# Server_Ethernet.net
KiCad netlist of a schematic drawn in Altium Designer
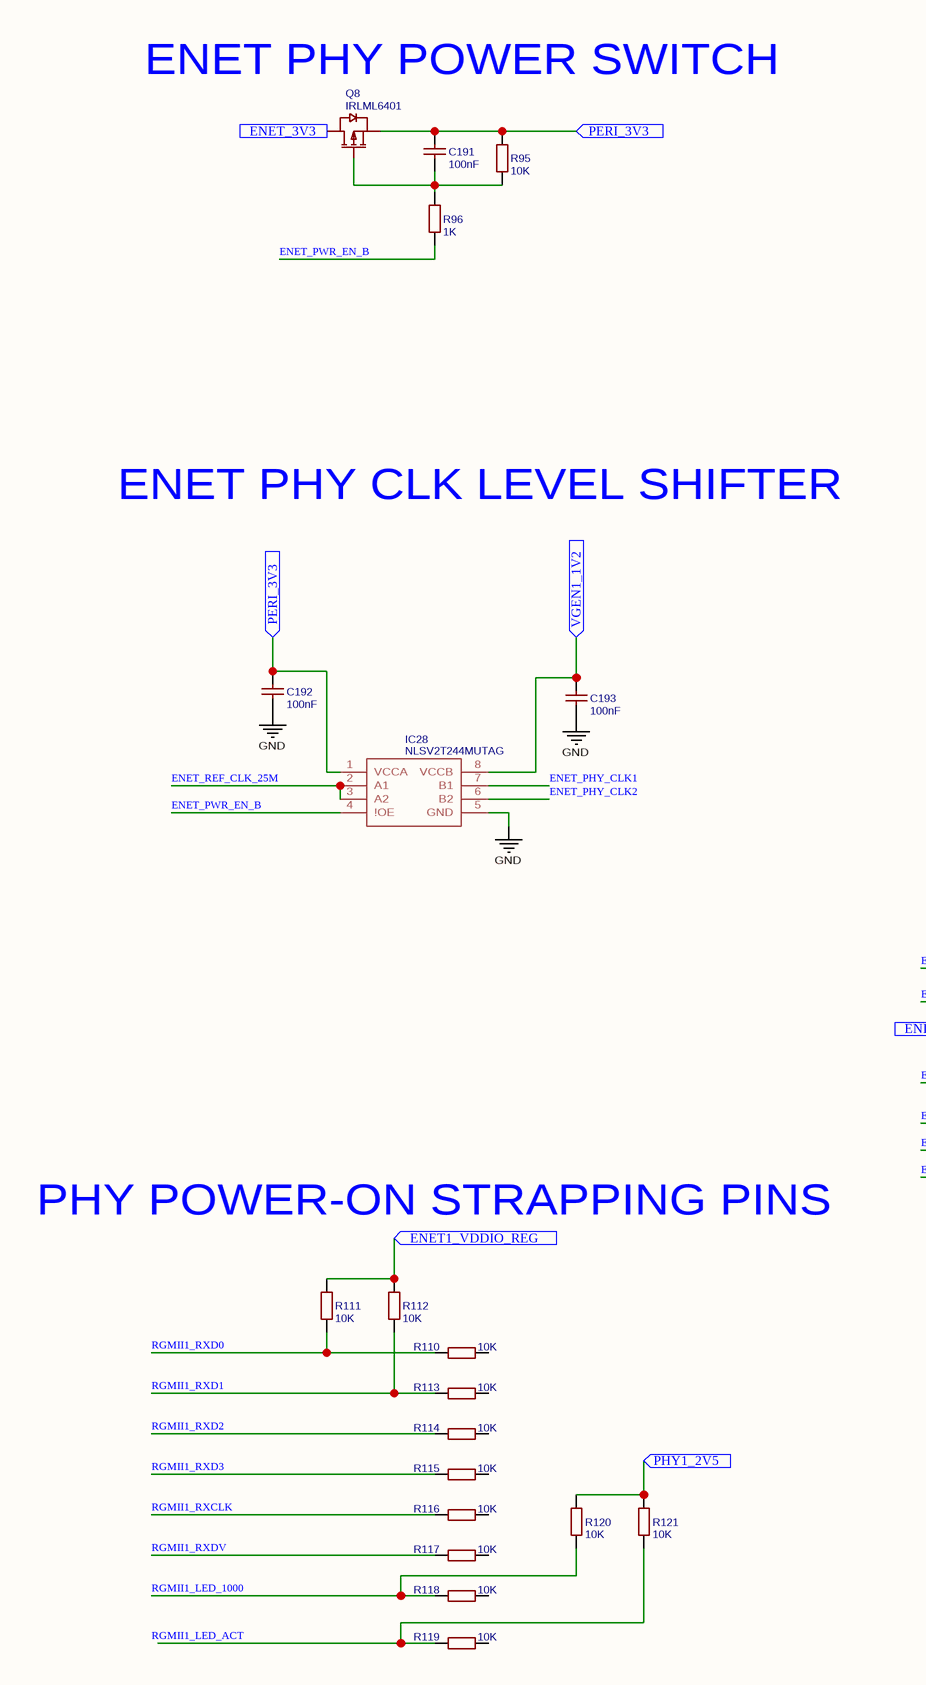
[diagram p0: Server Ethernet.schdoc, left]
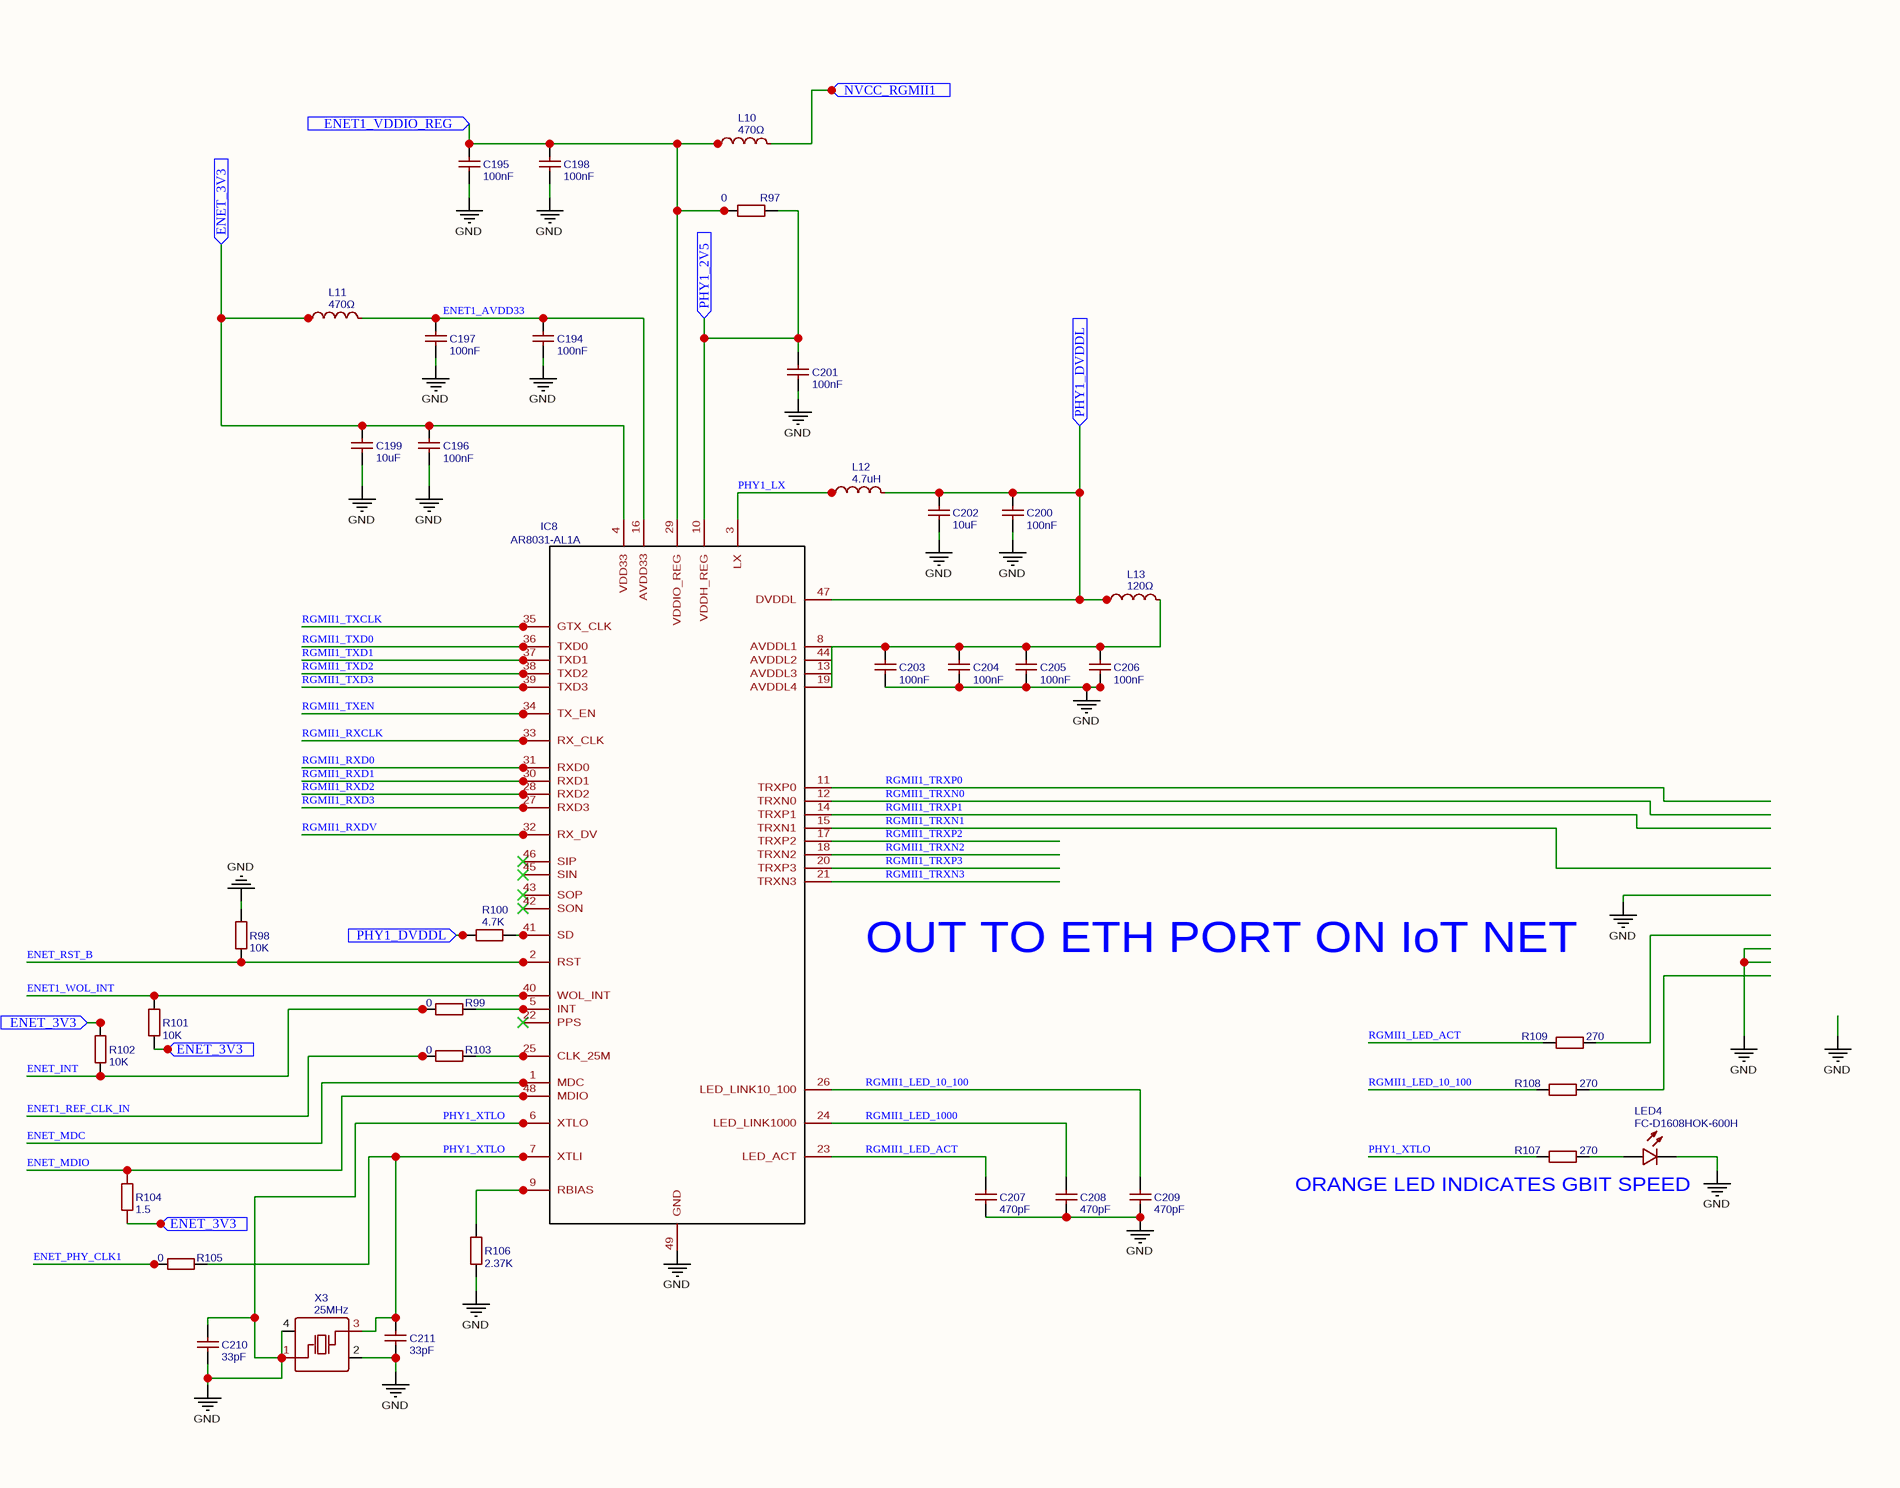
[diagram p1: Server Ethernet.schdoc, right]

(export (version "E")
  (design (tool "Eeschema 10.0.6"))
  (components
    (comp (ref "C191")
      (value "100nF")
      (fields
        (field (name "BOM_MANUFACTURER PART") "0603B104K250")
        (field (name "BOM_SUPPLIER PART") "C83054")
      )
      (libsource (lib "altium-import") (part "root_1_100nF_"))
    )
    (comp (ref "C192")
      (value "100nF")
      (fields
        (field (name "BOM_MANUFACTURER PART") "0603B104K250")
        (field (name "BOM_SUPPLIER PART") "C83054")
      )
      (libsource (lib "altium-import") (part "root_1_100nF_"))
    )
    (comp (ref "C193")
      (value "100nF")
      (fields
        (field (name "BOM_MANUFACTURER PART") "0603B104K250")
        (field (name "BOM_SUPPLIER PART") "C83054")
      )
      (libsource (lib "altium-import") (part "root_1_100nF_"))
    )
    (comp (ref "C194")
      (value "100nF")
      (fields
        (field (name "BOM_MANUFACTURER PART") "0603B104K250")
        (field (name "BOM_SUPPLIER PART") "C83054")
      )
      (libsource (lib "altium-import") (part "root_1_100nF_"))
    )
    (comp (ref "C195")
      (value "100nF")
      (fields
        (field (name "BOM_MANUFACTURER PART") "0603B104K250")
        (field (name "BOM_SUPPLIER PART") "C83054")
      )
      (libsource (lib "altium-import") (part "root_1_100nF_"))
    )
    (comp (ref "C196")
      (value "100nF")
      (fields
        (field (name "BOM_MANUFACTURER PART") "0603B104K250")
        (field (name "BOM_SUPPLIER PART") "C83054")
      )
      (libsource (lib "altium-import") (part "root_1_100nF_"))
    )
    (comp (ref "C197")
      (value "100nF")
      (fields
        (field (name "BOM_MANUFACTURER PART") "0603B104K250")
        (field (name "BOM_SUPPLIER PART") "C83054")
      )
      (libsource (lib "altium-import") (part "root_1_100nF_"))
    )
    (comp (ref "C198")
      (value "100nF")
      (fields
        (field (name "BOM_MANUFACTURER PART") "0603B104K250")
        (field (name "BOM_SUPPLIER PART") "C83054")
      )
      (libsource (lib "altium-import") (part "root_1_100nF_"))
    )
    (comp (ref "C199")
      (value "10uF")
      (fields
        (field (name "BOM_MANUFACTURER PART") "CL21A106KAYNNNE")
        (field (name "BOM_SUPPLIER PART") "C15850")
      )
      (libsource (lib "altium-import") (part "root_1_10uF_"))
    )
    (comp (ref "C200")
      (value "100nF")
      (fields
        (field (name "BOM_MANUFACTURER PART") "0603B104K250")
        (field (name "BOM_SUPPLIER PART") "C83054")
      )
      (libsource (lib "altium-import") (part "root_1_100nF_"))
    )
    (comp (ref "C201")
      (value "100nF")
      (fields
        (field (name "BOM_MANUFACTURER PART") "0603B104K250")
        (field (name "BOM_SUPPLIER PART") "C83054")
      )
      (libsource (lib "altium-import") (part "root_1_100nF_"))
    )
    (comp (ref "C202")
      (value "10uF")
      (fields
        (field (name "BOM_MANUFACTURER PART") "CL21A106KAYNNNE")
        (field (name "BOM_SUPPLIER PART") "C15850")
      )
      (libsource (lib "altium-import") (part "root_1_10uF_"))
    )
    (comp (ref "C203")
      (value "100nF")
      (fields
        (field (name "BOM_MANUFACTURER PART") "0603B104K250")
        (field (name "BOM_SUPPLIER PART") "C83054")
      )
      (libsource (lib "altium-import") (part "root_1_100nF_"))
    )
    (comp (ref "C204")
      (value "100nF")
      (fields
        (field (name "BOM_MANUFACTURER PART") "0603B104K250")
        (field (name "BOM_SUPPLIER PART") "C83054")
      )
      (libsource (lib "altium-import") (part "root_1_100nF_"))
    )
    (comp (ref "C205")
      (value "100nF")
      (fields
        (field (name "BOM_MANUFACTURER PART") "0603B104K250")
        (field (name "BOM_SUPPLIER PART") "C83054")
      )
      (libsource (lib "altium-import") (part "root_1_100nF_"))
    )
    (comp (ref "C206")
      (value "100nF")
      (fields
        (field (name "BOM_MANUFACTURER PART") "0603B104K250")
        (field (name "BOM_SUPPLIER PART") "C83054")
      )
      (libsource (lib "altium-import") (part "root_1_100nF_"))
    )
    (comp (ref "C207")
      (value "470pF")
      (fields
        (field (name "BOM_MANUFACTURER PART") "0805B471K500NT")
        (field (name "BOM_SUPPLIER PART") "C1743")
      )
      (libsource (lib "altium-import") (part "root_1_470pF_"))
    )
    (comp (ref "C208")
      (value "470pF")
      (fields
        (field (name "BOM_MANUFACTURER PART") "0805B471K500NT")
        (field (name "BOM_SUPPLIER PART") "C1743")
      )
      (libsource (lib "altium-import") (part "root_1_470pF_"))
    )
    (comp (ref "C209")
      (value "470pF")
      (fields
        (field (name "BOM_MANUFACTURER PART") "0805B471K500NT")
        (field (name "BOM_SUPPLIER PART") "C1743")
      )
      (libsource (lib "altium-import") (part "root_1_470pF_"))
    )
    (comp (ref "C210")
      (value "33pF")
      (fields
        (field (name "BOM_MANUFACTURER PART") "0402CG330J500NT")
        (field (name "BOM_SUPPLIER PART") "C1562")
      )
      (libsource (lib "altium-import") (part "root_1_33pF_"))
    )
    (comp (ref "C211")
      (value "33pF")
      (fields
        (field (name "BOM_MANUFACTURER PART") "0402CG330J500NT")
        (field (name "BOM_SUPPLIER PART") "C1562")
      )
      (libsource (lib "altium-import") (part "root_1_33pF_"))
    )
    (comp (ref "IC8")
      (value "AR8031-AL1A")
      (fields (field (name "CONTRIBUTOR") "Ke'Ondrae_Mell"))
      (libsource (lib "altium-import") (part "root_0_AR8031-AL1A_"))
    )
    (comp (ref "IC28")
      (value "NLSV2T244MUTAG")
      (fields (field (name "CONTRIBUTOR") "Ke'Ondrae_Mell"))
      (libsource (lib "altium-import") (part "root_0_NLSV2T244MUTAG_"))
    )
    (comp (ref "L10")
      (value "470Ω")
      (fields
        (field (name "BOM_MANUFACTURER PART") "GZ1608D471TF")
        (field (name "BOM_SUPPLIER PART") "C89921")
      )
      (libsource (lib "altium-import") (part "root_0_470Ω_"))
    )
    (comp (ref "L11")
      (value "470Ω")
      (fields
        (field (name "BOM_MANUFACTURER PART") "GZ1608D471TF")
        (field (name "BOM_SUPPLIER PART") "C89921")
      )
      (libsource (lib "altium-import") (part "root_0_470Ω_"))
    )
    (comp (ref "L12")
      (value "4.7uH")
      (fields
        (field (name "BOM_MANUFACTURER PART") "MLF2012A4R7KT000")
        (field (name "BOM_SUPPLIER PART") "C76736")
      )
      (libsource (lib "altium-import") (part "root_0_4.7uH_"))
    )
    (comp (ref "L13")
      (value "120Ω")
      (fields
        (field (name "BOM_MANUFACTURER PART") "BLM18PG121SN1D")
        (field (name "BOM_SUPPLIER PART") "C73100")
      )
      (libsource (lib "altium-import") (part "root_0_120Ω_"))
    )
    (comp (ref "LED4")
      (value "FC-D1608HOK-600H")
      (fields (field (name "BOM_SUPPLIER PART") "C84269"))
      (libsource (lib "altium-import") (part "root_0_FC-D1608HOK-600H_"))
    )
    (comp (ref "Q8")
      (value "IRLML6401")
      (fields (field (name "BOM_SUPPLIER PART") "C236925") (field (name "CONTRIBUTOR") "LCSC"))
      (libsource (lib "altium-import") (part "root_1_IRLML6401_"))
    )
    (comp (ref "R95")
      (value "10K")
      (fields
        (field (name "BOM_MANUFACTURER PART") "0402WGF1002TCE")
        (field (name "BOM_SUPPLIER PART") "C25744")
      )
      (libsource (lib "altium-import") (part "root_1_10K_"))
    )
    (comp (ref "R96")
      (value "1K")
      (fields
        (field (name "BOM_MANUFACTURER PART") "0402WGF1001TCE")
        (field (name "BOM_SUPPLIER PART") "C11702")
      )
      (libsource (lib "altium-import") (part "root_1_1K_"))
    )
    (comp (ref "R97")
      (value "0")
      (fields
        (field (name "BOM_MANUFACTURER PART") "RK73Z1ETTP")
        (field (name "BOM_SUPPLIER PART") "C131359")
      )
      (libsource (lib "altium-import") (part "root_0_0_"))
    )
    (comp (ref "R98")
      (value "10K")
      (fields
        (field (name "BOM_MANUFACTURER PART") "0402WGF1002TCE")
        (field (name "BOM_SUPPLIER PART") "C25744")
      )
      (libsource (lib "altium-import") (part "root_1_10K_"))
    )
    (comp (ref "R99")
      (value "0")
      (fields
        (field (name "BOM_MANUFACTURER PART") "RK73Z1ETTP")
        (field (name "BOM_SUPPLIER PART") "C131359")
      )
      (libsource (lib "altium-import") (part "root_0_0_"))
    )
    (comp (ref "R100")
      (value "4.7K")
      (fields
        (field (name "BOM_MANUFACTURER PART") "0402WGF4701TCE")
        (field (name "BOM_SUPPLIER PART") "C25900")
      )
      (libsource (lib "altium-import") (part "root_0_4.7K_"))
    )
    (comp (ref "R101")
      (value "10K")
      (fields
        (field (name "BOM_MANUFACTURER PART") "0402WGF1002TCE")
        (field (name "BOM_SUPPLIER PART") "C25744")
      )
      (libsource (lib "altium-import") (part "root_1_10K_"))
    )
    (comp (ref "R102")
      (value "10K")
      (fields
        (field (name "BOM_MANUFACTURER PART") "0402WGF1002TCE")
        (field (name "BOM_SUPPLIER PART") "C25744")
      )
      (libsource (lib "altium-import") (part "root_1_10K_"))
    )
    (comp (ref "R103")
      (value "0")
      (fields
        (field (name "BOM_MANUFACTURER PART") "RK73Z1ETTP")
        (field (name "BOM_SUPPLIER PART") "C131359")
      )
      (libsource (lib "altium-import") (part "root_0_0_"))
    )
    (comp (ref "R104")
      (value "1.5")
      (fields
        (field (name "BOM_SUPPLIER PART") "C270642")
        (field (name "BOM_MANUFACTURER PART") "0402WGF150KTCE")
        (field (name "CONTRIBUTOR") "LCSC")
      )
      (libsource (lib "altium-import") (part "root_1_1.5_"))
    )
    (comp (ref "R105")
      (value "0")
      (fields
        (field (name "BOM_MANUFACTURER PART") "RK73Z1ETTP")
        (field (name "BOM_SUPPLIER PART") "C131359")
      )
      (libsource (lib "altium-import") (part "root_0_0_"))
    )
    (comp (ref "R106")
      (value "2.37K")
      (fields
        (field (name "BOM_MANUFACTURER PART") "0402WGF2371TCE")
        (field (name "BOM_SUPPLIER PART") "C25881")
      )
      (libsource (lib "altium-import") (part "root_1_2.37K_"))
    )
    (comp (ref "R107")
      (value "270")
      (fields
        (field (name "BOM_MANUFACTURER PART") "0603WAF2700T5E")
        (field (name "BOM_SUPPLIER PART") "C22966")
      )
      (libsource (lib "altium-import") (part "root_0_270_"))
    )
    (comp (ref "R108")
      (value "270")
      (fields
        (field (name "BOM_MANUFACTURER PART") "0603WAF2700T5E")
        (field (name "BOM_SUPPLIER PART") "C22966")
      )
      (libsource (lib "altium-import") (part "root_0_270_"))
    )
    (comp (ref "R109")
      (value "270")
      (fields
        (field (name "BOM_MANUFACTURER PART") "0603WAF2700T5E")
        (field (name "BOM_SUPPLIER PART") "C22966")
      )
      (libsource (lib "altium-import") (part "root_0_270_"))
    )
    (comp (ref "R110")
      (value "10K")
      (fields
        (field (name "BOM_MANUFACTURER PART") "0402WGF1002TCE")
        (field (name "BOM_SUPPLIER PART") "C25744")
      )
      (libsource (lib "altium-import") (part "root_2_10K_"))
    )
    (comp (ref "R111")
      (value "10K")
      (fields
        (field (name "BOM_MANUFACTURER PART") "0402WGF1002TCE")
        (field (name "BOM_SUPPLIER PART") "C25744")
      )
      (libsource (lib "altium-import") (part "root_1_10K_"))
    )
    (comp (ref "R112")
      (value "10K")
      (fields
        (field (name "BOM_MANUFACTURER PART") "0402WGF1002TCE")
        (field (name "BOM_SUPPLIER PART") "C25744")
      )
      (libsource (lib "altium-import") (part "root_1_10K_"))
    )
    (comp (ref "R113")
      (value "10K")
      (fields
        (field (name "BOM_MANUFACTURER PART") "0402WGF1002TCE")
        (field (name "BOM_SUPPLIER PART") "C25744")
      )
      (libsource (lib "altium-import") (part "root_2_10K_"))
    )
    (comp (ref "R114")
      (value "10K")
      (fields
        (field (name "BOM_MANUFACTURER PART") "0402WGF1002TCE")
        (field (name "BOM_SUPPLIER PART") "C25744")
      )
      (libsource (lib "altium-import") (part "root_2_10K_"))
    )
    (comp (ref "R115")
      (value "10K")
      (fields
        (field (name "BOM_MANUFACTURER PART") "0402WGF1002TCE")
        (field (name "BOM_SUPPLIER PART") "C25744")
      )
      (libsource (lib "altium-import") (part "root_2_10K_"))
    )
    (comp (ref "R116")
      (value "10K")
      (fields
        (field (name "BOM_MANUFACTURER PART") "0402WGF1002TCE")
        (field (name "BOM_SUPPLIER PART") "C25744")
      )
      (libsource (lib "altium-import") (part "root_2_10K_"))
    )
    (comp (ref "R117")
      (value "10K")
      (fields
        (field (name "BOM_MANUFACTURER PART") "0402WGF1002TCE")
        (field (name "BOM_SUPPLIER PART") "C25744")
      )
      (libsource (lib "altium-import") (part "root_2_10K_"))
    )
    (comp (ref "R118")
      (value "10K")
      (fields
        (field (name "BOM_MANUFACTURER PART") "0402WGF1002TCE")
        (field (name "BOM_SUPPLIER PART") "C25744")
      )
      (libsource (lib "altium-import") (part "root_2_10K_"))
    )
    (comp (ref "R119")
      (value "10K")
      (fields
        (field (name "BOM_MANUFACTURER PART") "0402WGF1002TCE")
        (field (name "BOM_SUPPLIER PART") "C25744")
      )
      (libsource (lib "altium-import") (part "root_2_10K_"))
    )
    (comp (ref "R120")
      (value "10K")
      (fields
        (field (name "BOM_MANUFACTURER PART") "0402WGF1002TCE")
        (field (name "BOM_SUPPLIER PART") "C25744")
      )
      (libsource (lib "altium-import") (part "root_3_10K_"))
    )
    (comp (ref "R121")
      (value "10K")
      (fields
        (field (name "BOM_MANUFACTURER PART") "0402WGF1002TCE")
        (field (name "BOM_SUPPLIER PART") "C25744")
      )
      (libsource (lib "altium-import") (part "root_3_10K_"))
    )
    (comp (ref "X3")
      (value "25MHz")
      (fields
        (field (name "BOM_MANUFACTURER PART") "X322525MOB4SI")
        (field (name "BOM_SUPPLIER PART") "C9006")
      )
      (libsource (lib "altium-import") (part "root_0_25MHz_"))
    )
  )
  (nets
    (net (code "1") (name "/ENET1_AVDD33") (class "Default")
      (node (ref "C194") (pin "2") (pinfunction "2_2") (pintype "passive"))
      (node (ref "C197") (pin "2") (pinfunction "2_2") (pintype "passive"))
      (node (ref "IC8") (pin "16") (pinfunction "AVDD33_16") (pintype "passive"))
      (node (ref "L11") (pin "2") (pinfunction "2_2") (pintype "passive"))
    )
    (net (code "2") (name "/ENET1_REF_CLK_IN") (class "Default")
      (node (ref "R103") (pin "1") (pinfunction "1_1") (pintype "passive"))
    )
    (net (code "3") (name "/ENET1_VDDIO_REG") (class "Default")
      (node (ref "C195") (pin "2") (pinfunction "2_2") (pintype "passive"))
      (node (ref "C198") (pin "2") (pinfunction "2_2") (pintype "passive"))
      (node (ref "IC8") (pin "29") (pinfunction "VDDIO_REG_29") (pintype "passive"))
      (node (ref "L10") (pin "1") (pinfunction "1_1") (pintype "passive"))
      (node (ref "R111") (pin "2") (pinfunction "2_2") (pintype "passive"))
      (node (ref "R112") (pin "2") (pinfunction "2_2") (pintype "passive"))
      (node (ref "R97") (pin "1") (pinfunction "1_1") (pintype "passive"))
    )
    (net (code "4") (name "/ENET1_WOL_INT") (class "Default")
      (node (ref "IC8") (pin "40") (pinfunction "WOL_INT_40") (pintype "passive"))
      (node (ref "R101") (pin "2") (pinfunction "2_2") (pintype "passive"))
    )
    (net (code "5") (name "/ENET_3V3") (class "Default")
      (node (ref "C196") (pin "2") (pinfunction "2_2") (pintype "passive"))
      (node (ref "C199") (pin "2") (pinfunction "2_2") (pintype "passive"))
      (node (ref "IC8") (pin "4") (pinfunction "VDD33_4") (pintype "passive"))
      (node (ref "L11") (pin "1") (pinfunction "1_1") (pintype "passive"))
      (node (ref "Q8") (pin "3") (pinfunction "D_3") (pintype "passive"))
      (node (ref "R101") (pin "1") (pinfunction "1_1") (pintype "passive"))
      (node (ref "R102") (pin "2") (pinfunction "2_2") (pintype "passive"))
      (node (ref "R104") (pin "1") (pinfunction "1_1") (pintype "passive"))
    )
    (net (code "6") (name "/ENET_INT") (class "Default")
      (node (ref "R102") (pin "1") (pinfunction "1_1") (pintype "passive"))
      (node (ref "R99") (pin "1") (pinfunction "1_1") (pintype "passive"))
    )
    (net (code "7") (name "/ENET_MDC") (class "Default")
      (node (ref "IC8") (pin "1") (pinfunction "MDC_1") (pintype "passive"))
    )
    (net (code "8") (name "/ENET_MDIO") (class "Default")
      (node (ref "IC8") (pin "48") (pinfunction "MDIO_48") (pintype "passive"))
      (node (ref "R104") (pin "2") (pinfunction "2_2") (pintype "passive"))
    )
    (net (code "9") (name "/ENET_PHY_CLK1") (class "Default")
      (node (ref "IC28") (pin "7") (pinfunction "B1_7") (pintype "passive"))
      (node (ref "R105") (pin "1") (pinfunction "1_1") (pintype "passive"))
    )
    (net (code "10") (name "/ENET_PHY_CLK2") (class "Default")
      (node (ref "IC28") (pin "6") (pinfunction "B2_6") (pintype "passive"))
    )
    (net (code "11") (name "/ENET_PWR_EN_B") (class "Default")
      (node (ref "IC28") (pin "4") (pinfunction "!OE_4") (pintype "passive"))
      (node (ref "R96") (pin "1") (pinfunction "1_1") (pintype "passive"))
    )
    (net (code "12") (name "/ENET_REF_CLK_25M") (class "Default")
      (node (ref "IC28") (pin "2") (pinfunction "A1_2") (pintype "passive"))
      (node (ref "IC28") (pin "3") (pinfunction "A2_3") (pintype "passive"))
    )
    (net (code "13") (name "/ENET_RST_B") (class "Default")
      (node (ref "IC8") (pin "2") (pinfunction "RST_2") (pintype "passive"))
      (node (ref "R98") (pin "1") (pinfunction "1_1") (pintype "passive"))
    )
    (net (code "14") (name "/NVCC_RGMII1") (class "Default")
      (node (ref "L10") (pin "2") (pinfunction "2_2") (pintype "passive"))
    )
    (net (code "15") (name "/PERI_3V3") (class "Default")
      (node (ref "C191") (pin "2") (pinfunction "2_2") (pintype "passive"))
      (node (ref "C192") (pin "2") (pinfunction "2_2") (pintype "passive"))
      (node (ref "IC28") (pin "1") (pinfunction "VCCA_1") (pintype "passive"))
      (node (ref "Q8") (pin "2") (pinfunction "S_2") (pintype "passive"))
      (node (ref "R95") (pin "2") (pinfunction "2_2") (pintype "passive"))
    )
    (net (code "16") (name "/PHY1_2V5") (class "Default")
      (node (ref "C201") (pin "2") (pinfunction "2_2") (pintype "passive"))
      (node (ref "IC8") (pin "10") (pinfunction "VDDH_REG_10") (pintype "passive"))
      (node (ref "R120") (pin "1") (pinfunction "1_1") (pintype "passive"))
      (node (ref "R121") (pin "1") (pinfunction "1_1") (pintype "passive"))
      (node (ref "R97") (pin "2") (pinfunction "2_2") (pintype "passive"))
    )
    (net (code "17") (name "/PHY1_DVDDL") (class "Default")
      (node (ref "C200") (pin "2") (pinfunction "2_2") (pintype "passive"))
      (node (ref "C202") (pin "2") (pinfunction "2_2") (pintype "passive"))
      (node (ref "IC8") (pin "47") (pinfunction "DVDDL_47") (pintype "passive"))
      (node (ref "L12") (pin "2") (pinfunction "2_2") (pintype "passive"))
      (node (ref "L13") (pin "1") (pinfunction "1_1") (pintype "passive"))
      (node (ref "R100") (pin "1") (pinfunction "1_1") (pintype "passive"))
    )
    (net (code "18") (name "/PHY1_LX") (class "Default")
      (node (ref "IC8") (pin "3") (pinfunction "LX_3") (pintype "passive"))
      (node (ref "L12") (pin "1") (pinfunction "1_1") (pintype "passive"))
    )
    (net (code "19") (name "/RGMII1_LED_10_100") (class "Default")
      (node (ref "C209") (pin "2") (pinfunction "2_2") (pintype "passive"))
      (node (ref "IC8") (pin "26") (pinfunction "LED_LINK10_100_26") (pintype "passive"))
      (node (ref "R108") (pin "1") (pinfunction "1_1") (pintype "passive"))
    )
    (net (code "20") (name "/RGMII1_LED_1000") (class "Default")
      (node (ref "C208") (pin "2") (pinfunction "2_2") (pintype "passive"))
      (node (ref "IC8") (pin "24") (pinfunction "LED_LINK1000_24") (pintype "passive"))
      (node (ref "R118") (pin "2") (pinfunction "2_2") (pintype "passive"))
      (node (ref "R120") (pin "2") (pinfunction "2_2") (pintype "passive"))
    )
    (net (code "21") (name "/RGMII1_LED_ACT") (class "Default")
      (node (ref "C207") (pin "2") (pinfunction "2_2") (pintype "passive"))
      (node (ref "IC8") (pin "23") (pinfunction "LED_ACT_23") (pintype "passive"))
      (node (ref "R109") (pin "1") (pinfunction "1_1") (pintype "passive"))
    )
    (net (code "22") (name "/RGMII1_RXCLK") (class "Default")
      (node (ref "IC8") (pin "33") (pinfunction "RX_CLK_33") (pintype "passive"))
      (node (ref "R116") (pin "2") (pinfunction "2_2") (pintype "passive"))
    )
    (net (code "23") (name "/RGMII1_RXD0") (class "Default")
      (node (ref "IC8") (pin "31") (pinfunction "RXD0_31") (pintype "passive"))
      (node (ref "R110") (pin "2") (pinfunction "2_2") (pintype "passive"))
      (node (ref "R111") (pin "1") (pinfunction "1_1") (pintype "passive"))
    )
    (net (code "24") (name "/RGMII1_RXD1") (class "Default")
      (node (ref "IC8") (pin "30") (pinfunction "RXD1_30") (pintype "passive"))
      (node (ref "R112") (pin "1") (pinfunction "1_1") (pintype "passive"))
      (node (ref "R113") (pin "2") (pinfunction "2_2") (pintype "passive"))
    )
    (net (code "25") (name "/RGMII1_RXD2") (class "Default")
      (node (ref "IC8") (pin "28") (pinfunction "RXD2_28") (pintype "passive"))
      (node (ref "R114") (pin "2") (pinfunction "2_2") (pintype "passive"))
    )
    (net (code "26") (name "/RGMII1_RXD3") (class "Default")
      (node (ref "IC8") (pin "27") (pinfunction "RXD3_27") (pintype "passive"))
      (node (ref "R115") (pin "2") (pinfunction "2_2") (pintype "passive"))
    )
    (net (code "27") (name "/RGMII1_RXDV") (class "Default")
      (node (ref "IC8") (pin "32") (pinfunction "RX_DV_32") (pintype "passive"))
      (node (ref "R117") (pin "2") (pinfunction "2_2") (pintype "passive"))
    )
    (net (code "28") (name "/RGMII1_TRXN0") (class "Default")
      (node (ref "IC8") (pin "12") (pinfunction "TRXN0_12") (pintype "passive"))
    )
    (net (code "29") (name "/RGMII1_TRXN1") (class "Default")
      (node (ref "IC8") (pin "15") (pinfunction "TRXN1_15") (pintype "passive"))
    )
    (net (code "30") (name "/RGMII1_TRXN2") (class "Default")
      (node (ref "IC8") (pin "18") (pinfunction "TRXN2_18") (pintype "passive"))
    )
    (net (code "31") (name "/RGMII1_TRXN3") (class "Default")
      (node (ref "IC8") (pin "21") (pinfunction "TRXN3_21") (pintype "passive"))
    )
    (net (code "32") (name "/RGMII1_TRXP0") (class "Default")
      (node (ref "IC8") (pin "11") (pinfunction "TRXP0_11") (pintype "passive"))
    )
    (net (code "33") (name "/RGMII1_TRXP1") (class "Default")
      (node (ref "IC8") (pin "14") (pinfunction "TRXP1_14") (pintype "passive"))
    )
    (net (code "34") (name "/RGMII1_TRXP2") (class "Default")
      (node (ref "IC8") (pin "17") (pinfunction "TRXP2_17") (pintype "passive"))
    )
    (net (code "35") (name "/RGMII1_TRXP3") (class "Default")
      (node (ref "IC8") (pin "20") (pinfunction "TRXP3_20") (pintype "passive"))
    )
    (net (code "36") (name "/RGMII1_TXCLK") (class "Default")
      (node (ref "IC8") (pin "35") (pinfunction "GTX_CLK_35") (pintype "passive"))
    )
    (net (code "37") (name "/RGMII1_TXD0") (class "Default")
      (node (ref "IC8") (pin "36") (pinfunction "TXD0_36") (pintype "passive"))
    )
    (net (code "38") (name "/RGMII1_TXD1") (class "Default")
      (node (ref "IC8") (pin "37") (pinfunction "TXD1_37") (pintype "passive"))
    )
    (net (code "39") (name "/RGMII1_TXD2") (class "Default")
      (node (ref "IC8") (pin "38") (pinfunction "TXD2_38") (pintype "passive"))
    )
    (net (code "40") (name "/RGMII1_TXD3") (class "Default")
      (node (ref "IC8") (pin "39") (pinfunction "TXD3_39") (pintype "passive"))
    )
    (net (code "41") (name "/RGMII1_TXEN") (class "Default")
      (node (ref "IC8") (pin "34") (pinfunction "TX_EN_34") (pintype "passive"))
    )
    (net (code "42") (name "/VGEN1_1V2") (class "Default")
      (node (ref "C193") (pin "2") (pinfunction "2_2") (pintype "passive"))
      (node (ref "IC28") (pin "8") (pinfunction "VCCB_8") (pintype "passive"))
    )
    (net (code "43") (name "GND") (class "Default")
      (node (ref "C192") (pin "1") (pinfunction "1_1") (pintype "passive"))
      (node (ref "C193") (pin "1") (pinfunction "1_1") (pintype "passive"))
      (node (ref "C194") (pin "1") (pinfunction "1_1") (pintype "passive"))
      (node (ref "C195") (pin "1") (pinfunction "1_1") (pintype "passive"))
      (node (ref "C196") (pin "1") (pinfunction "1_1") (pintype "passive"))
      (node (ref "C197") (pin "1") (pinfunction "1_1") (pintype "passive"))
      (node (ref "C198") (pin "1") (pinfunction "1_1") (pintype "passive"))
      (node (ref "C199") (pin "1") (pinfunction "1_1") (pintype "passive"))
      (node (ref "C200") (pin "1") (pinfunction "1_1") (pintype "passive"))
      (node (ref "C201") (pin "1") (pinfunction "1_1") (pintype "passive"))
      (node (ref "C202") (pin "1") (pinfunction "1_1") (pintype "passive"))
      (node (ref "C203") (pin "1") (pinfunction "1_1") (pintype "passive"))
      (node (ref "C204") (pin "1") (pinfunction "1_1") (pintype "passive"))
      (node (ref "C205") (pin "1") (pinfunction "1_1") (pintype "passive"))
      (node (ref "C206") (pin "1") (pinfunction "1_1") (pintype "passive"))
      (node (ref "C207") (pin "1") (pinfunction "1_1") (pintype "passive"))
      (node (ref "C208") (pin "1") (pinfunction "1_1") (pintype "passive"))
      (node (ref "C209") (pin "1") (pinfunction "1_1") (pintype "passive"))
      (node (ref "C210") (pin "1") (pinfunction "1_1") (pintype "passive"))
      (node (ref "C210") (pin "2") (pinfunction "2_2") (pintype "passive"))
      (node (ref "C211") (pin "1") (pinfunction "1_1") (pintype "passive"))
      (node (ref "C211") (pin "2") (pinfunction "2_2") (pintype "passive"))
      (node (ref "IC28") (pin "5") (pinfunction "GND_5") (pintype "passive"))
      (node (ref "IC8") (pin "49") (pinfunction "GND_49") (pintype "passive"))
      (node (ref "IC8") (pin "6") (pinfunction "XTLO_6") (pintype "passive"))
      (node (ref "IC8") (pin "7") (pinfunction "XTLI_7") (pintype "passive"))
      (node (ref "LED4") (pin "1") (pinfunction "K_1") (pintype "passive"))
      (node (ref "R105") (pin "2") (pinfunction "2_2") (pintype "passive"))
      (node (ref "R106") (pin "1") (pinfunction "1_1") (pintype "passive"))
      (node (ref "R107") (pin "1") (pinfunction "1_1") (pintype "passive"))
      (node (ref "R98") (pin "2") (pinfunction "2_2") (pintype "passive"))
      (node (ref "X3") (pin "1") (pinfunction "OSC1_1") (pintype "passive"))
      (node (ref "X3") (pin "2") (pinfunction "GND_2") (pintype "passive"))
      (node (ref "X3") (pin "3") (pinfunction "OSC2_3") (pintype "passive"))
      (node (ref "X3") (pin "4") (pinfunction "GND_4") (pintype "passive"))
    )
    (net (code "44") (name "Net-(IC8-AVDDL1)") (class "Default")
      (node (ref "C203") (pin "2") (pinfunction "2_2") (pintype "passive"))
      (node (ref "C204") (pin "2") (pinfunction "2_2") (pintype "passive"))
      (node (ref "C205") (pin "2") (pinfunction "2_2") (pintype "passive"))
      (node (ref "C206") (pin "2") (pinfunction "2_2") (pintype "passive"))
      (node (ref "IC8") (pin "13") (pinfunction "AVDDL3_13") (pintype "passive"))
      (node (ref "IC8") (pin "19") (pinfunction "AVDDL4_19") (pintype "passive"))
      (node (ref "IC8") (pin "44") (pinfunction "AVDDL2_44") (pintype "passive"))
      (node (ref "IC8") (pin "8") (pinfunction "AVDDL1_8") (pintype "passive"))
      (node (ref "L13") (pin "2") (pinfunction "2_2") (pintype "passive"))
    )
    (net (code "45") (name "Net-(IC8-CLK_25M)") (class "Default")
      (node (ref "IC8") (pin "25") (pinfunction "CLK_25M_25") (pintype "passive"))
      (node (ref "R103") (pin "2") (pinfunction "2_2") (pintype "passive"))
    )
    (net (code "46") (name "Net-(IC8-INT)") (class "Default")
      (node (ref "IC8") (pin "5") (pinfunction "INT_5") (pintype "passive"))
      (node (ref "R99") (pin "2") (pinfunction "2_2") (pintype "passive"))
    )
    (net (code "47") (name "Net-(IC8-RBIAS)") (class "Default")
      (node (ref "IC8") (pin "9") (pinfunction "RBIAS_9") (pintype "passive"))
      (node (ref "R106") (pin "2") (pinfunction "2_2") (pintype "passive"))
    )
    (net (code "48") (name "Net-(IC8-SD)") (class "Default")
      (node (ref "IC8") (pin "41") (pinfunction "SD_41") (pintype "passive"))
      (node (ref "R100") (pin "2") (pinfunction "2_2") (pintype "passive"))
    )
    (net (code "49") (name "Net-(LED4-A)") (class "Default")
      (node (ref "LED4") (pin "2") (pinfunction "A_2") (pintype "passive"))
      (node (ref "R107") (pin "2") (pinfunction "2_2") (pintype "passive"))
    )
    (net (code "50") (name "Net-(Q8-G)") (class "Default")
      (node (ref "C191") (pin "1") (pinfunction "1_1") (pintype "passive"))
      (node (ref "Q8") (pin "1") (pinfunction "G_1") (pintype "passive"))
      (node (ref "R95") (pin "1") (pinfunction "1_1") (pintype "passive"))
      (node (ref "R96") (pin "2") (pinfunction "2_2") (pintype "passive"))
    )
    (net (code "51") (name "Net-(R119-Pad2)") (class "Default")
      (node (ref "R119") (pin "2") (pinfunction "2_2") (pintype "passive"))
      (node (ref "R121") (pin "2") (pinfunction "2_2") (pintype "passive"))
    )
    (net (code "52") (name "unconnected-(IC8-PPS-Pad22)") (class "Default")
      (node (ref "IC8") (pin "22") (pinfunction "PPS_22") (pintype "passive+no_connect"))
    )
    (net (code "53") (name "unconnected-(IC8-SIN-Pad45)") (class "Default")
      (node (ref "IC8") (pin "45") (pinfunction "SIN_45") (pintype "passive+no_connect"))
    )
    (net (code "54") (name "unconnected-(IC8-SIP-Pad46)") (class "Default")
      (node (ref "IC8") (pin "46") (pinfunction "SIP_46") (pintype "passive+no_connect"))
    )
    (net (code "55") (name "unconnected-(IC8-SON-Pad42)") (class "Default")
      (node (ref "IC8") (pin "42") (pinfunction "SON_42") (pintype "passive+no_connect"))
    )
    (net (code "56") (name "unconnected-(IC8-SOP-Pad43)") (class "Default")
      (node (ref "IC8") (pin "43") (pinfunction "SOP_43") (pintype "passive+no_connect"))
    )
    (net (code "57") (name "unconnected-(R108-Pad2)") (class "Default")
      (node (ref "R108") (pin "2") (pinfunction "2_2") (pintype "passive"))
    )
    (net (code "58") (name "unconnected-(R109-Pad2)") (class "Default")
      (node (ref "R109") (pin "2") (pinfunction "2_2") (pintype "passive"))
    )
    (net (code "59") (name "unconnected-(R110-Pad1)") (class "Default")
      (node (ref "R110") (pin "1") (pinfunction "1_1") (pintype "passive"))
    )
    (net (code "60") (name "unconnected-(R113-Pad1)") (class "Default")
      (node (ref "R113") (pin "1") (pinfunction "1_1") (pintype "passive"))
    )
    (net (code "61") (name "unconnected-(R114-Pad1)") (class "Default")
      (node (ref "R114") (pin "1") (pinfunction "1_1") (pintype "passive"))
    )
    (net (code "62") (name "unconnected-(R115-Pad1)") (class "Default")
      (node (ref "R115") (pin "1") (pinfunction "1_1") (pintype "passive"))
    )
    (net (code "63") (name "unconnected-(R116-Pad1)") (class "Default")
      (node (ref "R116") (pin "1") (pinfunction "1_1") (pintype "passive"))
    )
    (net (code "64") (name "unconnected-(R117-Pad1)") (class "Default")
      (node (ref "R117") (pin "1") (pinfunction "1_1") (pintype "passive"))
    )
    (net (code "65") (name "unconnected-(R118-Pad1)") (class "Default")
      (node (ref "R118") (pin "1") (pinfunction "1_1") (pintype "passive"))
    )
    (net (code "66") (name "unconnected-(R119-Pad1)") (class "Default")
      (node (ref "R119") (pin "1") (pinfunction "1_1") (pintype "passive"))
    )
  )
)
